# UBC-Thunderbots_PCB_Oven__PCB_Oven__PCB_.net
KiCad netlist of a schematic drawn in Altium Designer
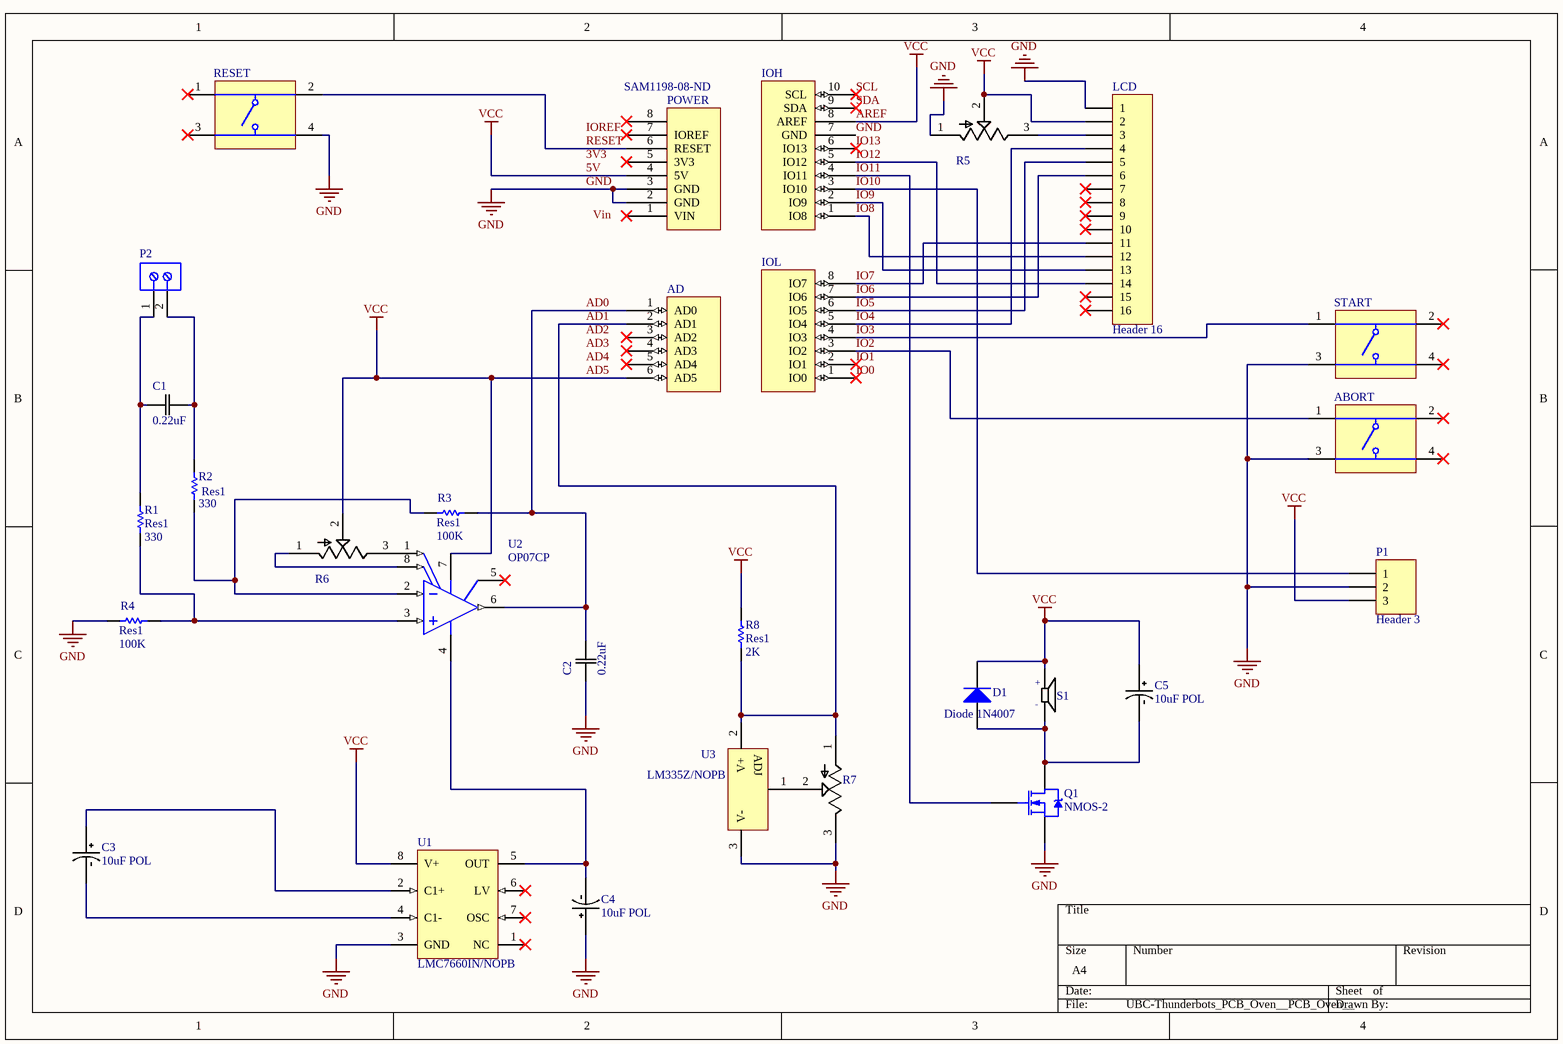
[diagram p0: UBC-Thunderbots_PCB_Oven__PCB_Oven__PCB_Oven_Sch.SchDoc]

(export (version "E")
  (design (tool "Eeschema 10.0.6"))
  (components
    (comp (ref "ABORT")
      (value "1825910-6")
      (footprint "TECO-1825910-6_V")
      (description "Tact Switch, SPST-NO, 0.05 A, -35 to 85 degC, 4-Pin THD, RoHS, Bulk")
      (fields (field (name "MANUFACTURER") "TE Connectivity"))
      (libsource (lib "Altium Content Vault") (part "SW-SPST-4_A"))
    )
    (comp (ref "AD")
      (value "AD")
      (footprint "Header:Header 6x1 8.5mm")
      (libsource (lib "Header") (part "AD"))
    )
    (comp (ref "C1")
      (value "0.22uF")
      (footprint "0.22uF Thru hole")
      (description "CAP CER 0.22UF 200V")
      (fields (field (name "MP") "C317C221K2G5TA7301") (field (name "MF") "KEMET"))
      (libsource (lib "AltiumLibraries") (part "CAP 0.22uF"))
    )
    (comp (ref "C2")
      (value "0.22uF")
      (footprint "0.22uF Thru hole")
      (description "CAP CER 0.22UF 200V")
      (fields (field (name "MP") "C317C221K2G5TA7301") (field (name "MF") "KEMET"))
      (libsource (lib "AltiumLibraries") (part "CAP 0.22uF"))
    )
    (comp (ref "C3")
      (value "10uF POL")
      (footprint "CAP POL 10uF THRU")
      (description "CAP ALUM 10UF 20% 50V RADIAL")
      (fields (field (name "TOLERANCE") "20%") (field (name "MP") "ECA-1HM100I"))
      (libsource (lib "AltiumLibraries") (part "CAP POL 10uF THRU"))
    )
    (comp (ref "C4")
      (value "10uF POL")
      (footprint "CAP POL 10uF THRU")
      (description "CAP ALUM 10UF 20% 50V RADIAL")
      (fields (field (name "TOLERANCE") "20%") (field (name "MP") "ECA-1HM100I"))
      (libsource (lib "AltiumLibraries") (part "CAP POL 10uF THRU"))
    )
    (comp (ref "C5")
      (value "10uF POL")
      (footprint "CAP POL 10uF THRU")
      (description "CAP ALUM 10UF 20% 50V RADIAL")
      (fields (field (name "TOLERANCE") "20%") (field (name "MP") "ECA-1HM100I"))
      (libsource (lib "AltiumLibraries") (part "CAP POL 10uF THRU"))
    )
    (comp (ref "D1")
      (value "Diode 1N4007")
      (footprint "DO-41")
      (description "1 Amp General Purpose Rectifier")
      (fields (field (name "PUBLISHER") "Altium Limited"))
      (libsource (lib "Miscellaneous Devices") (part "Diode 1N4007"))
    )
    (comp (ref "IOH")
      (value "IOH")
      (footprint "Header:Header 10x1 8.5mm")
      (libsource (lib "Header") (part "IOH"))
    )
    (comp (ref "IOL") (value "IOL") (footprint "Header 8x1 8.5mm") (libsource (lib "Header") (part "IOL")))
    (comp (ref "LCD")
      (value "Header 16")
      (footprint "HDR1X16")
      (description "Header, 16-Pin")
      (fields (field (name "PUBLISHER") "Altium Limited"))
      (libsource (lib "Miscellaneous Connectors") (part "Header 16"))
    )
    (comp (ref "P1")
      (value "Header 3")
      (footprint "HDR1X3")
      (description "Header, 3-Pin")
      (fields (field (name "PUBLISHER") "Altium Limited"))
      (libsource (lib "Miscellaneous Connectors") (part "Header 3"))
    )
    (comp (ref "P2")
      (value "282836-2")
      (footprint "TECO-282836-2_V")
      (description "Female Header, Pitch 5 mm, 1 x 2 Position, Height 10 mm, Tail Length 3.5 mm, Rohs, Bulk")
      (fields (field (name "VOLTAGE") "300V") (field (name "MANUFACTURER") "TE Connectivity"))
      (libsource (lib "Altium Content Vault") (part "CN-1P-F-TB2"))
    )
    (comp (ref "POWER")
      (value "POWER_UNO")
      (footprint "Header 8x1 8.5mm")
      (fields (field (name "SUPPLIER PART NUMBER 1") "SAM1198-08-ND"))
      (libsource (lib "Header") (part "POWER_UNO"))
    )
    (comp (ref "Q1")
      (value "NMOS-2")
      (footprint "TO-220AB")
      (libsource (lib "Miscellaneous Devices") (part "NMOS-2"))
    )
    (comp (ref "R1")
      (value "Res1")
      (footprint "AXIAL-0.3")
      (description "Resistor")
      (fields (field (name "ALTIUM_VALUE") "330") (field (name "PUBLISHER") "Altium Limited"))
      (libsource (lib "Miscellaneous Devices") (part "Res1"))
    )
    (comp (ref "R2")
      (value "Res1")
      (footprint "AXIAL-0.3")
      (description "Resistor")
      (fields (field (name "ALTIUM_VALUE") "330") (field (name "PUBLISHER") "Altium Limited"))
      (libsource (lib "Miscellaneous Devices") (part "Res1"))
    )
    (comp (ref "R3")
      (value "Res1")
      (footprint "AXIAL-0.3")
      (description "Resistor")
      (fields (field (name "ALTIUM_VALUE") "100K") (field (name "PUBLISHER") "Altium Limited"))
      (libsource (lib "Miscellaneous Devices") (part "Res1"))
    )
    (comp (ref "R4")
      (value "Res1")
      (footprint "AXIAL-0.3")
      (description "Resistor")
      (fields (field (name "ALTIUM_VALUE") "100K") (field (name "PUBLISHER") "Altium Limited"))
      (libsource (lib "Miscellaneous Devices") (part "Res1"))
    )
    (comp (ref "R5")
      (value "20K")
      (footprint "Potentiometer 20K")
      (description "TRIMMER 20K OHM 0.5W PC PIN TOP - Phillips Screw head")
      (fields (field (name "MF") "Bourns Inc.") (field (name "MP") "3362P-1-203RLF"))
      (libsource (lib "AltiumLibraries") (part "POT 20K THRU"))
    )
    (comp (ref "R6")
      (value "20K")
      (footprint "Potentiometer 20K")
      (description "TRIMMER 20K OHM 0.5W PC PIN TOP - Phillips Screw head")
      (fields (field (name "MF") "Bourns Inc.") (field (name "MP") "3362P-1-203RLF"))
      (libsource (lib "AltiumLibraries") (part "POT 20K THRU"))
    )
    (comp (ref "R7")
      (value "20K")
      (footprint "Potentiometer 20K")
      (description "TRIMMER 20K OHM 0.5W PC PIN TOP - Phillips Screw head")
      (fields (field (name "MF") "Bourns Inc.") (field (name "MP") "3362P-1-203RLF"))
      (libsource (lib "AltiumLibraries") (part "POT 20K THRU"))
    )
    (comp (ref "R8")
      (value "Res1")
      (footprint "AXIAL-0.3")
      (description "Resistor")
      (fields (field (name "ALTIUM_VALUE") "2K") (field (name "PUBLISHER") "Altium Limited"))
      (libsource (lib "Miscellaneous Devices") (part "Res1"))
    )
    (comp (ref "RESET")
      (value "1825910-6")
      (footprint "TECO-1825910-6_V")
      (description "Tact Switch, SPST-NO, 0.05 A, -35 to 85 degC, 4-Pin THD, RoHS, Bulk")
      (fields (field (name "MANUFACTURER") "TE Connectivity"))
      (libsource (lib "Altium Content Vault") (part "SW-SPST-4_A"))
    )
    (comp (ref "S1")
      (value "CEM-1203(42) THRU")
      (footprint "CEM-1203")
      (description "35mA 2.048kHz 85dB @ 3.5V")
      (fields (field (name "MP") "CEM-1203(42)") (field (name "MF") "CUI Devices"))
      (libsource (lib "AltiumLibraries") (part "CEM-1203(42) THRU"))
    )
    (comp (ref "START")
      (value "1825910-6")
      (footprint "TECO-1825910-6_V")
      (description "Tact Switch, SPST-NO, 0.05 A, -35 to 85 degC, 4-Pin THD, RoHS, Bulk")
      (fields (field (name "MANUFACTURER") "TE Connectivity"))
      (libsource (lib "Altium Content Vault") (part "SW-SPST-4_A"))
    )
    (comp (ref "U1")
      (value "LMC7660IN/NOPB")
      (footprint "P0008A")
      (description "Switched Capacitor Voltage Converter, 8-pin MDIP, Pb-Free")
      (fields (field (name "MANUFACTURER") "Texas Instruments"))
      (libsource (lib "Altium Content Vault") (part "PM-CHP-LMC7660IM-8"))
    )
    (comp (ref "U2")
      (value "OP07CP")
      (footprint "P0008A")
      (description "Low-Offset Voltage Operational Amplifier, 6 to 36 V, 0 to 70 degC, 8-pin DIP (P8), Pb-Free (RoHS)")
      (fields (field (name "MANUFACTURER") "Texas Instruments"))
      (libsource (lib "Altium Content Vault") (part "TI-OP07X-X8"))
    )
    (comp (ref "U3")
      (value "LM335Z/NOPB")
      (footprint "LP0003A")
      (description "Precision Temperature Sensor, 3-pin TO-92, Pb-Free")
      (fields (field (name "MANUFACTURER") "Texas Instruments"))
      (libsource (lib "Altium Content Vault") (part "SEN-TEMP-LM335-3"))
    )
  )
  (nets
    (net (code "3") (name "/AD0") (class "Default")
      (node (ref "AD") (pin "1") (pinfunction "AD0_1") (pintype "bidirectional"))
      (node (ref "C2") (pin "2") (pinfunction "C2_2") (pintype "passive"))
      (node (ref "R3") (pin "1") (pinfunction "1_1") (pintype "passive"))
      (node (ref "U2") (pin "6") (pinfunction "OUT_6") (pintype "output"))
    )
    (net (code "4") (name "/AD1") (class "Default")
      (node (ref "AD") (pin "2") (pinfunction "AD1_2") (pintype "bidirectional"))
      (node (ref "R7") (pin "1") (pinfunction "CCW_1") (pintype "passive"))
      (node (ref "R8") (pin "2") (pinfunction "2_2") (pintype "passive"))
      (node (ref "U3") (pin "2") (pinfunction "V+_2") (pintype "passive"))
    )
    (net (code "8") (name "/IO0") (class "Default")
      (node (ref "IOL") (pin "1") (pinfunction "IO0_1") (pintype "bidirectional+no_connect"))
    )
    (net (code "9") (name "/IO1") (class "Default")
      (node (ref "IOL") (pin "2") (pinfunction "IO1_2") (pintype "bidirectional+no_connect"))
    )
    (net (code "10") (name "/IO2") (class "Default")
      (node (ref "ABORT") (pin "1") (pinfunction "1_1") (pintype "passive"))
      (node (ref "IOL") (pin "3") (pinfunction "IO2_3") (pintype "bidirectional"))
    )
    (net (code "11") (name "/IO3") (class "Default")
      (node (ref "IOL") (pin "4") (pinfunction "IO3_4") (pintype "bidirectional"))
      (node (ref "START") (pin "1") (pinfunction "1_1") (pintype "passive"))
    )
    (net (code "12") (name "/IO4") (class "Default")
      (node (ref "IOL") (pin "5") (pinfunction "IO4_5") (pintype "bidirectional"))
      (node (ref "LCD") (pin "4") (pinfunction "4_4") (pintype "passive"))
    )
    (net (code "13") (name "/IO5") (class "Default")
      (node (ref "IOL") (pin "6") (pinfunction "IO5_6") (pintype "bidirectional"))
      (node (ref "LCD") (pin "5") (pinfunction "5_5") (pintype "passive"))
    )
    (net (code "14") (name "/IO6") (class "Default")
      (node (ref "IOL") (pin "7") (pinfunction "IO6_7") (pintype "bidirectional"))
      (node (ref "LCD") (pin "6") (pinfunction "6_6") (pintype "passive"))
    )
    (net (code "15") (name "/IO7") (class "Default")
      (node (ref "IOL") (pin "8") (pinfunction "IO7_8") (pintype "bidirectional"))
      (node (ref "LCD") (pin "11") (pinfunction "11_11") (pintype "passive"))
    )
    (net (code "16") (name "/IO8") (class "Default")
      (node (ref "IOH") (pin "1") (pinfunction "IO8_1") (pintype "bidirectional"))
      (node (ref "LCD") (pin "12") (pinfunction "12_12") (pintype "passive"))
    )
    (net (code "17") (name "/IO9") (class "Default")
      (node (ref "IOH") (pin "2") (pinfunction "IO9_2") (pintype "bidirectional"))
      (node (ref "LCD") (pin "13") (pinfunction "13_13") (pintype "passive"))
    )
    (net (code "18") (name "/IO10") (class "Default")
      (node (ref "IOH") (pin "3") (pinfunction "IO10_3") (pintype "bidirectional"))
      (node (ref "P1") (pin "1") (pinfunction "1_1") (pintype "passive"))
    )
    (net (code "19") (name "/IO11") (class "Default")
      (node (ref "IOH") (pin "4") (pinfunction "IO11_4") (pintype "bidirectional"))
      (node (ref "Q1") (pin "1") (pinfunction "G_1") (pintype "passive"))
    )
    (net (code "20") (name "/IO12") (class "Default")
      (node (ref "IOH") (pin "5") (pinfunction "IO12_5") (pintype "bidirectional"))
      (node (ref "LCD") (pin "14") (pinfunction "14_14") (pintype "passive"))
    )
    (net (code "21") (name "/IO13") (class "Default")
      (node (ref "IOH") (pin "6") (pinfunction "IO13_6") (pintype "bidirectional+no_connect"))
    )
    (net (code "23") (name "/RESET") (class "Default")
      (node (ref "POWER") (pin "6") (pinfunction "RESET_6") (pintype "passive"))
      (node (ref "RESET") (pin "2") (pinfunction "2_2") (pintype "passive"))
    )
    (net (code "24") (name "/SCL") (class "Default")
      (node (ref "IOH") (pin "10") (pinfunction "SCL_10") (pintype "bidirectional+no_connect"))
    )
    (net (code "25") (name "/SDA") (class "Default")
      (node (ref "IOH") (pin "9") (pinfunction "SDA_9") (pintype "bidirectional+no_connect"))
    )
    (net (code "27") (name "GND") (class "Default")
      (node (ref "ABORT") (pin "3") (pinfunction "3_3") (pintype "passive"))
      (node (ref "C2") (pin "1") (pinfunction "C1_1") (pintype "passive"))
      (node (ref "C4") (pin "POS") (pinfunction "POS_POS") (pintype "passive"))
      (node (ref "IOH") (pin "7") (pinfunction "GND_7") (pintype "power_in"))
      (node (ref "LCD") (pin "1") (pinfunction "1_1") (pintype "passive"))
      (node (ref "P1") (pin "2") (pinfunction "2_2") (pintype "passive"))
      (node (ref "POWER") (pin "2") (pinfunction "GND_2") (pintype "power_in"))
      (node (ref "POWER") (pin "3") (pinfunction "GND_3") (pintype "power_in"))
      (node (ref "Q1") (pin "3") (pinfunction "S_3") (pintype "passive"))
      (node (ref "R4") (pin "2") (pinfunction "2_2") (pintype "passive"))
      (node (ref "R5") (pin "1") (pinfunction "CCW_1") (pintype "passive"))
      (node (ref "R7") (pin "3") (pinfunction "CW_3") (pintype "passive"))
      (node (ref "RESET") (pin "4") (pinfunction "4_4") (pintype "passive"))
      (node (ref "START") (pin "3") (pinfunction "3_3") (pintype "passive"))
      (node (ref "U1") (pin "3") (pinfunction "GND_3") (pintype "power_in"))
      (node (ref "U3") (pin "3") (pinfunction "V-_3") (pintype "passive"))
    )
    (net (code "28") (name "Net-(C1-C1)") (class "Default")
      (node (ref "C1") (pin "1") (pinfunction "C1_1") (pintype "passive"))
      (node (ref "P2") (pin "1") (pinfunction "1_1") (pintype "passive"))
      (node (ref "R1") (pin "2") (pinfunction "2_2") (pintype "passive"))
    )
    (net (code "29") (name "Net-(C1-C2)") (class "Default")
      (node (ref "C1") (pin "2") (pinfunction "C2_2") (pintype "passive"))
      (node (ref "P2") (pin "2") (pinfunction "2_2") (pintype "passive"))
      (node (ref "R2") (pin "2") (pinfunction "2_2") (pintype "passive"))
    )
    (net (code "30") (name "Net-(D1-A)") (class "Default")
      (node (ref "C5") (pin "NEG") (pinfunction "NEG_NEG") (pintype "passive"))
      (node (ref "D1") (pin "1") (pinfunction "A_1") (pintype "passive"))
      (node (ref "Q1") (pin "2") (pinfunction "D_2") (pintype "passive"))
      (node (ref "S1") (pin "N") (pinfunction "N_N") (pintype "passive"))
    )
    (net (code "31") (name "Net-(R5-CW)") (class "Default")
      (node (ref "LCD") (pin "3") (pinfunction "3_3") (pintype "passive"))
      (node (ref "R5") (pin "3") (pinfunction "CW_3") (pintype "passive"))
    )
    (net (code "32") (name "Net-(R6-CCW)") (class "Default")
      (node (ref "R6") (pin "1") (pinfunction "CCW_1") (pintype "passive"))
      (node (ref "U2") (pin "8") (pinfunction "OFFSET_N2_8") (pintype "input"))
    )
    (net (code "33") (name "Net-(R6-CW)") (class "Default")
      (node (ref "R6") (pin "3") (pinfunction "CW_3") (pintype "passive"))
      (node (ref "U2") (pin "1") (pinfunction "OFFSET_N1_1") (pintype "input"))
    )
    (net (code "34") (name "Net-(R7-WIPER)") (class "Default")
      (node (ref "R7") (pin "2") (pinfunction "WIPER_2") (pintype "passive"))
      (node (ref "U3") (pin "1") (pinfunction "ADJ_1") (pintype "passive"))
    )
    (net (code "35") (name "Net-(U1-C1+)") (class "Default")
      (node (ref "C3") (pin "POS") (pinfunction "POS_POS") (pintype "passive"))
      (node (ref "U1") (pin "2") (pinfunction "C1+_2") (pintype "input"))
    )
    (net (code "36") (name "Net-(U1-C1-)") (class "Default")
      (node (ref "C3") (pin "NEG") (pinfunction "NEG_NEG") (pintype "passive"))
      (node (ref "U1") (pin "4") (pinfunction "C1-_4") (pintype "input"))
    )
    (net (code "37") (name "Net-(U1-OUT)") (class "Default")
      (node (ref "C4") (pin "NEG") (pinfunction "NEG_NEG") (pintype "passive"))
      (node (ref "U1") (pin "5") (pinfunction "OUT_5") (pintype "power_in"))
      (node (ref "U2") (pin "4") (pinfunction "VCC-_4") (pintype "power_in"))
    )
    (net (code "38") (name "Net-(U2-IN+)") (class "Default")
      (node (ref "R1") (pin "1") (pinfunction "1_1") (pintype "passive"))
      (node (ref "R4") (pin "1") (pinfunction "1_1") (pintype "passive"))
      (node (ref "U2") (pin "3") (pinfunction "IN+_3") (pintype "input"))
    )
    (net (code "39") (name "Net-(U2-IN-)") (class "Default")
      (node (ref "R2") (pin "1") (pinfunction "1_1") (pintype "passive"))
      (node (ref "R3") (pin "2") (pinfunction "2_2") (pintype "passive"))
      (node (ref "U2") (pin "2") (pinfunction "IN-_2") (pintype "input"))
    )
    (net (code "40") (name "VCC") (class "Default")
      (node (ref "AD") (pin "6") (pinfunction "AD5_6") (pintype "bidirectional"))
      (node (ref "C5") (pin "POS") (pinfunction "POS_POS") (pintype "passive"))
      (node (ref "D1") (pin "2") (pinfunction "K_2") (pintype "passive"))
      (node (ref "IOH") (pin "8") (pinfunction "AREF_8") (pintype "passive"))
      (node (ref "LCD") (pin "2") (pinfunction "2_2") (pintype "passive"))
      (node (ref "P1") (pin "3") (pinfunction "3_3") (pintype "passive"))
      (node (ref "POWER") (pin "4") (pinfunction "5V_4") (pintype "power_in"))
      (node (ref "R5") (pin "2") (pinfunction "WIPER_2") (pintype "passive"))
      (node (ref "R6") (pin "2") (pinfunction "WIPER_2") (pintype "passive"))
      (node (ref "R8") (pin "1") (pinfunction "1_1") (pintype "passive"))
      (node (ref "S1") (pin "P") (pinfunction "P_P") (pintype "passive"))
      (node (ref "U1") (pin "8") (pinfunction "V+_8") (pintype "power_in"))
      (node (ref "U2") (pin "7") (pinfunction "VCC+_7") (pintype "power_in"))
    )
    (net (code "41") (name "unconnected-(ABORT-Pad2)") (class "Default")
      (node (ref "ABORT") (pin "2") (pinfunction "2_2") (pintype "passive+no_connect"))
    )
    (net (code "42") (name "unconnected-(ABORT-Pad4)") (class "Default")
      (node (ref "ABORT") (pin "4") (pinfunction "4_4") (pintype "passive+no_connect"))
    )
    (net (code "43") (name "unconnected-(AD-AD2-Pad3)") (class "Default")
      (node (ref "AD") (pin "3") (pinfunction "AD2_3") (pintype "bidirectional+no_connect"))
    )
    (net (code "44") (name "unconnected-(AD-AD3-Pad4)") (class "Default")
      (node (ref "AD") (pin "4") (pinfunction "AD3_4") (pintype "bidirectional+no_connect"))
    )
    (net (code "45") (name "unconnected-(AD-AD4-Pad5)") (class "Default")
      (node (ref "AD") (pin "5") (pinfunction "AD4_5") (pintype "bidirectional+no_connect"))
    )
    (net (code "46") (name "unconnected-(LCD-Pad7)") (class "Default")
      (node (ref "LCD") (pin "7") (pinfunction "7_7") (pintype "passive+no_connect"))
    )
    (net (code "47") (name "unconnected-(LCD-Pad8)") (class "Default")
      (node (ref "LCD") (pin "8") (pinfunction "8_8") (pintype "passive+no_connect"))
    )
    (net (code "48") (name "unconnected-(LCD-Pad9)") (class "Default")
      (node (ref "LCD") (pin "9") (pinfunction "9_9") (pintype "passive+no_connect"))
    )
    (net (code "49") (name "unconnected-(LCD-Pad10)") (class "Default")
      (node (ref "LCD") (pin "10") (pinfunction "10_10") (pintype "passive+no_connect"))
    )
    (net (code "50") (name "unconnected-(LCD-Pad15)") (class "Default")
      (node (ref "LCD") (pin "15") (pinfunction "15_15") (pintype "passive+no_connect"))
    )
    (net (code "51") (name "unconnected-(LCD-Pad16)") (class "Default")
      (node (ref "LCD") (pin "16") (pinfunction "16_16") (pintype "passive+no_connect"))
    )
    (net (code "52") (name "unconnected-(POWER-3V3-Pad5)") (class "Default")
      (node (ref "POWER") (pin "5") (pinfunction "3V3_5") (pintype "power_in+no_connect"))
    )
    (net (code "53") (name "unconnected-(POWER-IOREF-Pad7)") (class "Default")
      (node (ref "POWER") (pin "7") (pinfunction "IOREF_7") (pintype "power_in+no_connect"))
    )
    (net (code "54") (name "unconnected-(POWER-Pad8)") (class "Default")
      (node (ref "POWER") (pin "8") (pintype "passive+no_connect"))
    )
    (net (code "55") (name "unconnected-(POWER-VIN-Pad1)") (class "Default")
      (node (ref "POWER") (pin "1") (pinfunction "VIN_1") (pintype "power_in+no_connect"))
    )
    (net (code "56") (name "unconnected-(RESET-Pad1)") (class "Default")
      (node (ref "RESET") (pin "1") (pinfunction "1_1") (pintype "passive+no_connect"))
    )
    (net (code "57") (name "unconnected-(RESET-Pad3)") (class "Default")
      (node (ref "RESET") (pin "3") (pinfunction "3_3") (pintype "passive+no_connect"))
    )
    (net (code "58") (name "unconnected-(START-Pad2)") (class "Default")
      (node (ref "START") (pin "2") (pinfunction "2_2") (pintype "passive+no_connect"))
    )
    (net (code "59") (name "unconnected-(START-Pad4)") (class "Default")
      (node (ref "START") (pin "4") (pinfunction "4_4") (pintype "passive+no_connect"))
    )
    (net (code "60") (name "unconnected-(U1-LV-Pad6)") (class "Default")
      (node (ref "U1") (pin "6") (pinfunction "LV_6") (pintype "input+no_connect"))
    )
    (net (code "61") (name "unconnected-(U1-NC-Pad1)") (class "Default")
      (node (ref "U1") (pin "1") (pinfunction "NC_1") (pintype "passive+no_connect"))
    )
    (net (code "62") (name "unconnected-(U1-OSC-Pad7)") (class "Default")
      (node (ref "U1") (pin "7") (pinfunction "OSC_7") (pintype "input+no_connect"))
    )
    (net (code "63") (name "unconnected-(U2-NC-Pad5)") (class "Default")
      (node (ref "U2") (pin "5") (pinfunction "NC_5") (pintype "passive+no_connect"))
    )
  )
)
